# ATmega328P.net
KiCad netlist of a schematic drawn in EAGLE
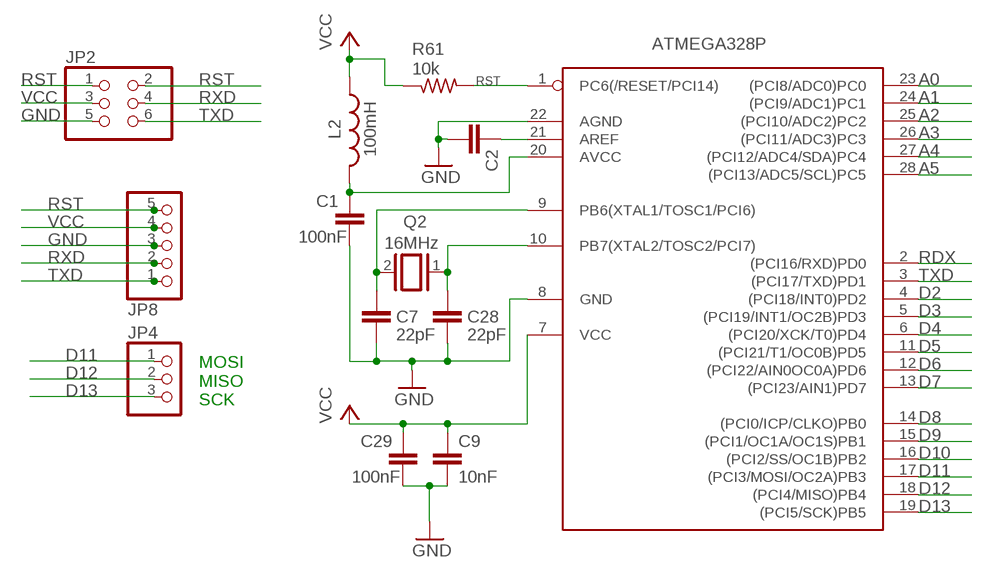
[diagram p0: schematic, sheet 1]

(export (version "E")
  (design (tool "Eeschema 10.0.6"))
  (components
    (comp (ref "C1")
      (value "100nF")
      (footprint "eagle-import:C050-024X044")
      (libsource (lib "eagle-import") (part "C-EU050-024X044"))
    )
    (comp (ref "C2")
      (value "C-EU050-024X044")
      (footprint "eagle-import:C050-024X044")
      (libsource (lib "eagle-import") (part "C-EU050-024X044"))
    )
    (comp (ref "C7")
      (value "22pF")
      (footprint "eagle-import:C050-024X044")
      (libsource (lib "eagle-import") (part "C-EU050-024X044"))
    )
    (comp (ref "C9")
      (value "10nF")
      (footprint "eagle-import:C050-024X044")
      (libsource (lib "eagle-import") (part "C-EU050-024X044"))
    )
    (comp (ref "C28")
      (value "22pF")
      (footprint "eagle-import:C050-024X044")
      (libsource (lib "eagle-import") (part "C-EU050-024X044"))
    )
    (comp (ref "C29")
      (value "100nF")
      (footprint "eagle-import:C050-024X044")
      (libsource (lib "eagle-import") (part "C-EU050-024X044"))
    )
    (comp (ref "IC7")
      (value "ATMEGA328P")
      (footprint "eagle-import:DIL28-3")
      (libsource (lib "eagle-import") (part "ATMEGA168P-20"))
    )
    (comp (ref "JP2")
      (value "PINHD-2X3")
      (footprint "eagle-import:2X03")
      (libsource (lib "eagle-import") (part "PINHD-2X3"))
    )
    (comp (ref "JP4")
      (value "PINHD-1X3")
      (footprint "eagle-import:1X03")
      (libsource (lib "eagle-import") (part "PINHD-1X3"))
    )
    (comp (ref "JP8")
      (value "PINHD-1X5/90")
      (footprint "eagle-import:1X05_90")
      (libsource (lib "eagle-import") (part "PINHD-1X5/90"))
    )
    (comp (ref "L2")
      (value "100mH")
      (footprint "eagle-import:0207_10")
      (libsource (lib "eagle-import") (part "L-US0207/10"))
    )
    (comp (ref "Q2")
      (value "16MHz")
      (footprint "eagle-import:QS")
      (libsource (lib "eagle-import") (part "XTAL/S"))
    )
    (comp (ref "R61")
      (value "10k")
      (footprint "eagle-import:0204_7")
      (libsource (lib "eagle-import") (part "R-US_0204/7"))
    )
  )
  (nets
    (net (code "1") (name "/A0") (class "Default")
      (node (ref "IC7") (pin "23") (pinfunction "(PCI8/ADC0)PC0_23") (pintype "bidirectional"))
    )
    (net (code "2") (name "/A1") (class "Default")
      (node (ref "IC7") (pin "24") (pinfunction "(PCI9/ADC1)PC1_24") (pintype "bidirectional"))
    )
    (net (code "3") (name "/A2") (class "Default")
      (node (ref "IC7") (pin "25") (pinfunction "(PCI10/ADC2)PC2_25") (pintype "bidirectional"))
    )
    (net (code "4") (name "/A3") (class "Default")
      (node (ref "IC7") (pin "26") (pinfunction "(PCI11/ADC3)PC3_26") (pintype "bidirectional"))
    )
    (net (code "5") (name "/A4") (class "Default")
      (node (ref "IC7") (pin "27") (pinfunction "(PCI12/ADC4/SDA)PC4_27") (pintype "bidirectional"))
    )
    (net (code "6") (name "/A5") (class "Default")
      (node (ref "IC7") (pin "28") (pinfunction "(PCI13/ADC5/SCL)PC5_28") (pintype "bidirectional"))
    )
    (net (code "7") (name "/D2") (class "Default")
      (node (ref "IC7") (pin "4") (pinfunction "(PCI18/INT0)PD2_4") (pintype "bidirectional"))
    )
    (net (code "8") (name "/D3") (class "Default")
      (node (ref "IC7") (pin "5") (pinfunction "(PCI19/INT1/OC2B)PD3_5") (pintype "bidirectional"))
    )
    (net (code "9") (name "/D4") (class "Default")
      (node (ref "IC7") (pin "6") (pinfunction "(PCI20/XCK/T0)PD4_6") (pintype "bidirectional"))
    )
    (net (code "10") (name "/D5") (class "Default")
      (node (ref "IC7") (pin "11") (pinfunction "(PCI21/T1/OC0B)PD5_11") (pintype "bidirectional"))
    )
    (net (code "11") (name "/D6") (class "Default")
      (node (ref "IC7") (pin "12") (pinfunction "(PCI22/AIN0OC0A)PD6_12") (pintype "bidirectional"))
    )
    (net (code "12") (name "/D7") (class "Default")
      (node (ref "IC7") (pin "13") (pinfunction "(PCI23/AIN1)PD7_13") (pintype "bidirectional"))
    )
    (net (code "13") (name "/D8") (class "Default")
      (node (ref "IC7") (pin "14") (pinfunction "(PCI0/ICP/CLKO)PB0_14") (pintype "bidirectional"))
    )
    (net (code "14") (name "/D9") (class "Default")
      (node (ref "IC7") (pin "15") (pinfunction "(PCI1/OC1A/OC1S)PB1_15") (pintype "bidirectional"))
    )
    (net (code "15") (name "/D10") (class "Default")
      (node (ref "IC7") (pin "16") (pinfunction "(PCI2/SS/OC1B)PB2_16") (pintype "bidirectional"))
    )
    (net (code "16") (name "/D11") (class "Default")
      (node (ref "IC7") (pin "17") (pinfunction "(PCI3/MOSI/OC2A)PB3_17") (pintype "bidirectional"))
      (node (ref "JP4") (pin "1") (pinfunction "1_1") (pintype "passive"))
    )
    (net (code "17") (name "/D12") (class "Default")
      (node (ref "IC7") (pin "18") (pinfunction "(PCI4/MISO)PB4_18") (pintype "bidirectional"))
      (node (ref "JP4") (pin "2") (pinfunction "2_2") (pintype "passive"))
    )
    (net (code "18") (name "/D13") (class "Default")
      (node (ref "IC7") (pin "19") (pinfunction "(PCI5/SCK)PB5_19") (pintype "bidirectional"))
      (node (ref "JP4") (pin "3") (pinfunction "3_3") (pintype "passive"))
    )
    (net (code "19") (name "/RDX") (class "Default")
      (node (ref "IC7") (pin "2") (pinfunction "(PCI16/RXD)PD0_2") (pintype "bidirectional"))
    )
    (net (code "20") (name "/RST") (class "Default")
      (node (ref "IC7") (pin "1") (pinfunction "PC6(/RESET/PCI14)_1") (pintype "bidirectional"))
      (node (ref "JP2") (pin "1") (pinfunction "1_1") (pintype "passive"))
      (node (ref "JP2") (pin "2") (pinfunction "2_2") (pintype "passive"))
      (node (ref "JP8") (pin "5") (pinfunction "5_5") (pintype "passive"))
      (node (ref "R61") (pin "2") (pinfunction "2_2") (pintype "passive"))
    )
    (net (code "21") (name "/RXD") (class "Default")
      (node (ref "JP2") (pin "4") (pinfunction "4_4") (pintype "passive"))
      (node (ref "JP8") (pin "2") (pinfunction "2_2") (pintype "passive"))
    )
    (net (code "22") (name "/TXD") (class "Default")
      (node (ref "IC7") (pin "3") (pinfunction "(PCI17/TXD)PD1_3") (pintype "bidirectional"))
      (node (ref "JP2") (pin "6") (pinfunction "6_6") (pintype "passive"))
      (node (ref "JP8") (pin "1") (pinfunction "1_1") (pintype "passive"))
    )
    (net (code "23") (name "GND") (class "Default")
      (node (ref "C1") (pin "2") (pinfunction "2_2") (pintype "passive"))
      (node (ref "C2") (pin "2") (pinfunction "2_2") (pintype "passive"))
      (node (ref "C28") (pin "2") (pinfunction "2_2") (pintype "passive"))
      (node (ref "C29") (pin "2") (pinfunction "2_2") (pintype "passive"))
      (node (ref "C7") (pin "2") (pinfunction "2_2") (pintype "passive"))
      (node (ref "C9") (pin "2") (pinfunction "2_2") (pintype "passive"))
      (node (ref "IC7") (pin "22") (pinfunction "AGND_22") (pintype "bidirectional"))
      (node (ref "IC7") (pin "8") (pinfunction "GND_8") (pintype "bidirectional"))
      (node (ref "JP2") (pin "5") (pinfunction "5_5") (pintype "passive"))
      (node (ref "JP8") (pin "3") (pinfunction "3_3") (pintype "passive"))
    )
    (net (code "24") (name "Net-(IC7-AREF)") (class "Default")
      (node (ref "C2") (pin "1") (pinfunction "1_1") (pintype "passive"))
      (node (ref "IC7") (pin "21") (pinfunction "AREF_21") (pintype "bidirectional"))
    )
    (net (code "25") (name "Net-(IC7-AVCC)") (class "Default")
      (node (ref "C1") (pin "1") (pinfunction "1_1") (pintype "passive"))
      (node (ref "IC7") (pin "20") (pinfunction "AVCC_20") (pintype "bidirectional"))
      (node (ref "L2") (pin "2") (pinfunction "2_2") (pintype "passive"))
    )
    (net (code "26") (name "Net-(IC7-PB6(XTAL1{slash}TOSC1{slash}PCI6))") (class "Default")
      (node (ref "C7") (pin "1") (pinfunction "1_1") (pintype "passive"))
      (node (ref "IC7") (pin "9") (pinfunction "PB6(XTAL1/TOSC1/PCI6)_9") (pintype "bidirectional"))
      (node (ref "Q2") (pin "2") (pinfunction "2_2") (pintype "passive"))
    )
    (net (code "27") (name "Net-(IC7-PB7(XTAL2{slash}TOSC2{slash}PCI7))") (class "Default")
      (node (ref "C28") (pin "1") (pinfunction "1_1") (pintype "passive"))
      (node (ref "IC7") (pin "10") (pinfunction "PB7(XTAL2/TOSC2/PCI7)_10") (pintype "bidirectional"))
      (node (ref "Q2") (pin "1") (pinfunction "1_1") (pintype "passive"))
    )
    (net (code "28") (name "VCC") (class "Default")
      (node (ref "C29") (pin "1") (pinfunction "1_1") (pintype "passive"))
      (node (ref "C9") (pin "1") (pinfunction "1_1") (pintype "passive"))
      (node (ref "IC7") (pin "7") (pinfunction "VCC_7") (pintype "bidirectional"))
      (node (ref "JP2") (pin "3") (pinfunction "3_3") (pintype "passive"))
      (node (ref "JP8") (pin "4") (pinfunction "4_4") (pintype "passive"))
      (node (ref "L2") (pin "1") (pinfunction "1_1") (pintype "passive"))
      (node (ref "R61") (pin "1") (pinfunction "1_1") (pintype "passive"))
    )
  )
)
